# ArduSensor-Temp.net
KiCad netlist of a schematic drawn in EAGLE
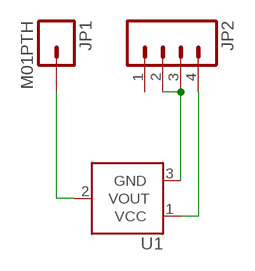
[diagram p0: schematic, sheet 1]

(export (version "E")
  (design (tool "Eeschema 10.0.6"))
  (components
    (comp (ref "JP1")
      (value "M01PTH")
      (footprint "eagle-import:1X01")
      (libsource (lib "eagle-import") (part "M01PTH"))
    )
    (comp (ref "JP2")
      (value "M04PTH")
      (footprint "eagle-import:1X04")
      (libsource (lib "eagle-import") (part "M04PTH"))
    )
    (comp (ref "U1")
      (value "TMP36GT9")
      (footprint "eagle-import:TO-92")
      (libsource (lib "eagle-import") (part "TMP36GT9"))
    )
  )
  (nets
    (net (code "1") (name "Net-(U1-GND)") (class "Default")
      (node (ref "JP2") (pin "2") (pinfunction "2_2") (pintype "passive"))
      (node (ref "JP2") (pin "3") (pinfunction "3_3") (pintype "passive"))
      (node (ref "U1") (pin "3") (pinfunction "GND_3") (pintype "bidirectional"))
    )
    (net (code "2") (name "Net-(U1-VCC)") (class "Default")
      (node (ref "JP2") (pin "4") (pinfunction "4_4") (pintype "passive"))
      (node (ref "U1") (pin "1") (pinfunction "VCC_1") (pintype "bidirectional"))
    )
    (net (code "3") (name "Net-(U1-VOUT)") (class "Default")
      (node (ref "JP1") (pin "1") (pinfunction "1_1") (pintype "passive"))
      (node (ref "U1") (pin "2") (pinfunction "VOUT_2") (pintype "bidirectional"))
    )
    (net (code "4") (name "unconnected-(JP2-Pad1)") (class "Default")
      (node (ref "JP2") (pin "1") (pinfunction "1_1") (pintype "passive"))
    )
  )
)
